# TopSheet.net
KiCad netlist of a schematic drawn in Altium Designer
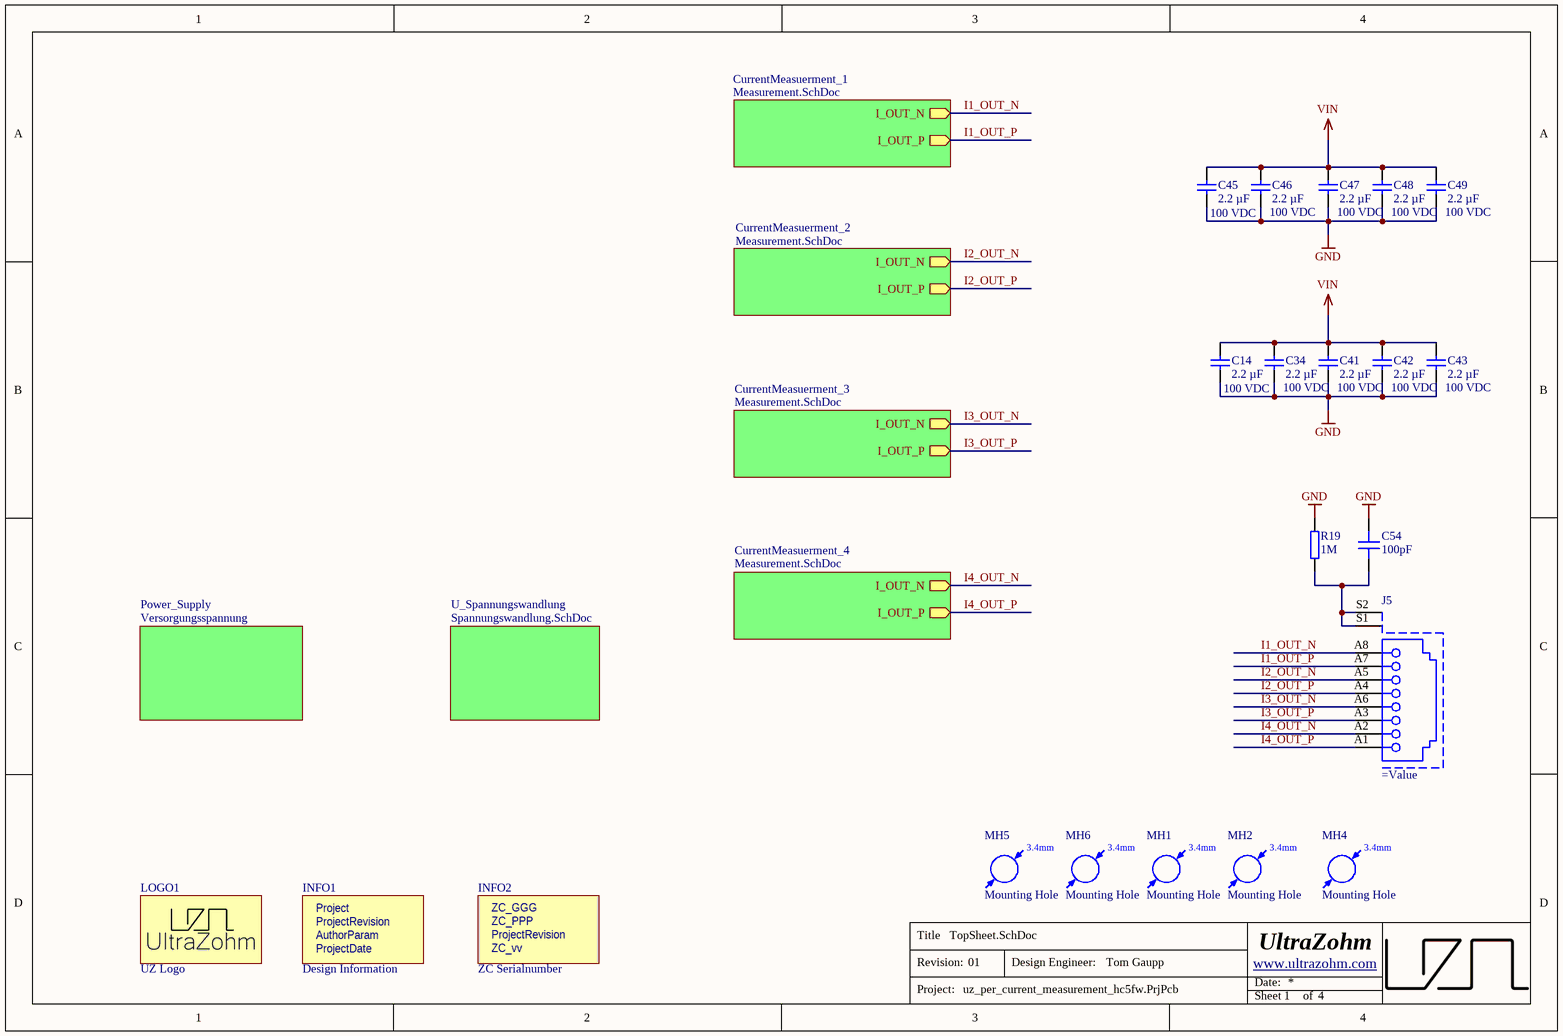
[diagram p0: TopSheet.SchDoc]

(export (version "E")
  (design (tool "Eeschema 10.0.6"))
  (components
    (comp (ref "C14")
      (value "2.2 µF")
      (footprint "C_1210_TE")
      (description "100V 2.2uF X7R ±10% 1210 Multilayer Ceramic Capacitors MLCC - SMD/SMT ROHS")
      (fields
        (field (name "MANUFACTURER PART NUMBER") "FS32X225K101EGG")
        (field (name "MANUFACTURER") "PSA(Prosperity Dielectrics)")
        (field (name "VOLTAGE RATING") "100 VDC")
        (field (name "CREATED FROM") "AGeiger")
      )
      (libsource (lib "user") (part "CAP-NP"))
    )
    (comp (ref "C34")
      (value "2.2 µF")
      (footprint "C_1210_TE")
      (description "100V 2.2uF X7R ±10% 1210 Multilayer Ceramic Capacitors MLCC - SMD/SMT ROHS")
      (fields
        (field (name "MANUFACTURER PART NUMBER") "FS32X225K101EGG")
        (field (name "MANUFACTURER") "PSA(Prosperity Dielectrics)")
        (field (name "VOLTAGE RATING") "100 VDC")
        (field (name "CREATED FROM") "AGeiger")
      )
      (libsource (lib "user") (part "CAP-NP"))
    )
    (comp (ref "C41")
      (value "2.2 µF")
      (footprint "C_1210_TE")
      (description "100V 2.2uF X7R ±10% 1210 Multilayer Ceramic Capacitors MLCC - SMD/SMT ROHS")
      (fields
        (field (name "MANUFACTURER PART NUMBER") "FS32X225K101EGG")
        (field (name "MANUFACTURER") "PSA(Prosperity Dielectrics)")
        (field (name "VOLTAGE RATING") "100 VDC")
        (field (name "CREATED FROM") "AGeiger")
      )
      (libsource (lib "user") (part "CAP-NP"))
    )
    (comp (ref "C42")
      (value "2.2 µF")
      (footprint "C_1210_TE")
      (description "100V 2.2uF X7R ±10% 1210 Multilayer Ceramic Capacitors MLCC - SMD/SMT ROHS")
      (fields
        (field (name "MANUFACTURER PART NUMBER") "FS32X225K101EGG")
        (field (name "MANUFACTURER") "PSA(Prosperity Dielectrics)")
        (field (name "VOLTAGE RATING") "100 VDC")
        (field (name "CREATED FROM") "AGeiger")
      )
      (libsource (lib "user") (part "CAP-NP"))
    )
    (comp (ref "C43")
      (value "2.2 µF")
      (footprint "C_1210_TE")
      (description "100V 2.2uF X7R ±10% 1210 Multilayer Ceramic Capacitors MLCC - SMD/SMT ROHS")
      (fields
        (field (name "MANUFACTURER PART NUMBER") "FS32X225K101EGG")
        (field (name "MANUFACTURER") "PSA(Prosperity Dielectrics)")
        (field (name "VOLTAGE RATING") "100 VDC")
        (field (name "CREATED FROM") "AGeiger")
      )
      (libsource (lib "user") (part "CAP-NP"))
    )
    (comp (ref "C45")
      (value "2.2 µF")
      (footprint "C_1210_TE")
      (description "100V 2.2uF X7R ±10% 1210 Multilayer Ceramic Capacitors MLCC - SMD/SMT ROHS")
      (fields
        (field (name "MANUFACTURER PART NUMBER") "FS32X225K101EGG")
        (field (name "MANUFACTURER") "PSA(Prosperity Dielectrics)")
        (field (name "VOLTAGE RATING") "100 VDC")
        (field (name "CREATED FROM") "AGeiger")
      )
      (libsource (lib "user") (part "CAP-NP"))
    )
    (comp (ref "C46")
      (value "2.2 µF")
      (footprint "C_1210_TE")
      (description "100V 2.2uF X7R ±10% 1210 Multilayer Ceramic Capacitors MLCC - SMD/SMT ROHS")
      (fields
        (field (name "MANUFACTURER PART NUMBER") "FS32X225K101EGG")
        (field (name "MANUFACTURER") "PSA(Prosperity Dielectrics)")
        (field (name "VOLTAGE RATING") "100 VDC")
        (field (name "CREATED FROM") "AGeiger")
      )
      (libsource (lib "user") (part "CAP-NP"))
    )
    (comp (ref "C47")
      (value "2.2 µF")
      (footprint "C_1210_TE")
      (description "100V 2.2uF X7R ±10% 1210 Multilayer Ceramic Capacitors MLCC - SMD/SMT ROHS")
      (fields
        (field (name "MANUFACTURER PART NUMBER") "FS32X225K101EGG")
        (field (name "MANUFACTURER") "PSA(Prosperity Dielectrics)")
        (field (name "VOLTAGE RATING") "100 VDC")
        (field (name "CREATED FROM") "AGeiger")
      )
      (libsource (lib "user") (part "CAP-NP"))
    )
    (comp (ref "C48")
      (value "2.2 µF")
      (footprint "C_1210_TE")
      (description "100V 2.2uF X7R ±10% 1210 Multilayer Ceramic Capacitors MLCC - SMD/SMT ROHS")
      (fields
        (field (name "MANUFACTURER PART NUMBER") "FS32X225K101EGG")
        (field (name "MANUFACTURER") "PSA(Prosperity Dielectrics)")
        (field (name "VOLTAGE RATING") "100 VDC")
        (field (name "CREATED FROM") "AGeiger")
      )
      (libsource (lib "user") (part "CAP-NP"))
    )
    (comp (ref "C49")
      (value "2.2 µF")
      (footprint "C_1210_TE")
      (description "100V 2.2uF X7R ±10% 1210 Multilayer Ceramic Capacitors MLCC - SMD/SMT ROHS")
      (fields
        (field (name "MANUFACTURER PART NUMBER") "FS32X225K101EGG")
        (field (name "MANUFACTURER") "PSA(Prosperity Dielectrics)")
        (field (name "VOLTAGE RATING") "100 VDC")
        (field (name "CREATED FROM") "AGeiger")
      )
      (libsource (lib "user") (part "CAP-NP"))
    )
    (comp (ref "C54")
      (value "100pF")
      (footprint "C_1206_TE")
      (description "100pF 1kV C0G ±5% 1206 Multilayer Ceramic Capacitors MLCC - SMD/SMT ROHS")
      (fields
        (field (name "MANUFACTURER PART NUMBER") "1206CG101J102NT")
        (field (name "MANUFACTURER") "FH (Guangdong Fenghua Advanced Tech)")
        (field (name "CREATED FROM") "TGaupp")
      )
      (libsource (lib "user") (part "Capacitor"))
    )
    (comp (ref "INFO1")
      (value "Design Information")
      (footprint "Design_info")
      (fields (field (name "MANUFACTURER") "UltraZohm") (field (name "CREATED FROM") "MGremer"))
      (libsource (lib "user") (part "Design_info"))
    )
    (comp (ref "INFO2")
      (value "ZC Serialnumber")
      (footprint "ZC-Serial")
      (fields
        (field (name "MANUFACTURER PART NUMBER") "ZC-Serial")
        (field (name "MANUFACTURER") "UltraZohm")
        (field (name "CREATED FROM") "FRosner")
      )
      (libsource (lib "user") (part "ZC_Serial"))
    )
    (comp (ref "J5")
      (value "~")
      (footprint "R-RJ45R10P-B000")
      (fields
        (field (name "MANUFACTURER PART NUMBER") "R-RJ45R10P-B000")
        (field (name "MANUFACTURER") "Ckmtw(Shenzhen Cankemeng)")
        (field (name "LCSC PART NUMBER") "C386758")
        (field (name "CREATED FROM") "KIlhan")
      )
      (libsource (lib "user") (part "R-RJ45R10P-B000"))
    )
    (comp (ref "LOGO1")
      (value "UZ Logo")
      (footprint "UZ_Logo_small")
      (fields
        (field (name "MANUFACTURER PART NUMBER") "Logo small")
        (field (name "MANUFACTURER") "UltraZohm")
        (field (name "CREATED") "Jan2021_Liegmann")
        (field (name "CREATED FROM") "MGremer")
      )
      (libsource (lib "user") (part "UZ Logo"))
    )
    (comp (ref "MH1")
      (value "Mounting Hole")
      (footprint "MH_3.4")
      (fields (field (name "CREATED FROM") "MHlatky"))
      (libsource (lib "user") (part "Mounting Hole"))
    )
    (comp (ref "MH2")
      (value "Mounting Hole")
      (footprint "MH_3.4")
      (fields (field (name "CREATED FROM") "MHlatky"))
      (libsource (lib "user") (part "Mounting Hole"))
    )
    (comp (ref "MH4")
      (value "Mounting Hole")
      (footprint "MH_3.4")
      (fields (field (name "CREATED FROM") "MHlatky"))
      (libsource (lib "user") (part "Mounting Hole"))
    )
    (comp (ref "MH5")
      (value "Mounting Hole")
      (footprint "MH_3.4")
      (fields (field (name "CREATED FROM") "MHlatky"))
      (libsource (lib "user") (part "Mounting Hole"))
    )
    (comp (ref "MH6")
      (value "Mounting Hole")
      (footprint "MH_3.4")
      (fields (field (name "CREATED FROM") "MHlatky"))
      (libsource (lib "user") (part "Mounting Hole"))
    )
    (comp (ref "R19")
      (value "1M")
      (footprint "RES 0603_1608")
      (description "SMD resistor 1%")
      (fields
        (field (name "MANUFACTURER PART NUMBER") "CRCW06031M00FKEAC")
        (field (name "MANUFACTURER") "Vishay / Dale")
        (field (name "CREATED FROM") "MGremer")
      )
      (libsource (lib "user") (part "Resistor"))
    )
  )
  (nets
    (net (code "1") (name "/I1_OUT_N") (class "Default")
      (node (ref "J5") (pin "A8") (pinfunction "A8_A8") (pintype "passive"))
    )
    (net (code "2") (name "/I1_OUT_P") (class "Default")
      (node (ref "J5") (pin "A7") (pinfunction "A7_A7") (pintype "passive"))
    )
    (net (code "3") (name "/I2_OUT_N") (class "Default")
      (node (ref "J5") (pin "A5") (pinfunction "A5_A5") (pintype "passive"))
    )
    (net (code "4") (name "/I2_OUT_P") (class "Default")
      (node (ref "J5") (pin "A4") (pinfunction "A4_A4") (pintype "passive"))
    )
    (net (code "5") (name "/I3_OUT_N") (class "Default")
      (node (ref "J5") (pin "A6") (pinfunction "A6_A6") (pintype "passive"))
    )
    (net (code "6") (name "/I3_OUT_P") (class "Default")
      (node (ref "J5") (pin "A3") (pinfunction "A3_A3") (pintype "passive"))
    )
    (net (code "7") (name "/I4_OUT_N") (class "Default")
      (node (ref "J5") (pin "A2") (pinfunction "A2_A2") (pintype "passive"))
    )
    (net (code "8") (name "/I4_OUT_P") (class "Default")
      (node (ref "J5") (pin "A1") (pinfunction "A1_A1") (pintype "passive"))
    )
    (net (code "9") (name "GND") (class "Default")
      (node (ref "C14") (pin "2") (pinfunction "2_2") (pintype "passive"))
      (node (ref "C34") (pin "2") (pinfunction "2_2") (pintype "passive"))
      (node (ref "C41") (pin "2") (pinfunction "2_2") (pintype "passive"))
      (node (ref "C42") (pin "2") (pinfunction "2_2") (pintype "passive"))
      (node (ref "C43") (pin "2") (pinfunction "2_2") (pintype "passive"))
      (node (ref "C45") (pin "2") (pinfunction "2_2") (pintype "passive"))
      (node (ref "C46") (pin "2") (pinfunction "2_2") (pintype "passive"))
      (node (ref "C47") (pin "2") (pinfunction "2_2") (pintype "passive"))
      (node (ref "C48") (pin "2") (pinfunction "2_2") (pintype "passive"))
      (node (ref "C49") (pin "2") (pinfunction "2_2") (pintype "passive"))
      (node (ref "C54") (pin "2") (pinfunction "2_2") (pintype "passive"))
      (node (ref "R19") (pin "2") (pinfunction "2_2") (pintype "passive"))
    )
    (net (code "10") (name "Net-(C54-Pad1)") (class "Default")
      (node (ref "C54") (pin "1") (pinfunction "1_1") (pintype "passive"))
      (node (ref "J5") (pin "S1") (pinfunction "S1_S1") (pintype "passive"))
      (node (ref "J5") (pin "S2") (pinfunction "S2_S2") (pintype "passive"))
      (node (ref "R19") (pin "1") (pinfunction "1_1") (pintype "passive"))
    )
    (net (code "11") (name "VIN") (class "Default")
      (node (ref "C14") (pin "1") (pinfunction "1_1") (pintype "passive"))
      (node (ref "C34") (pin "1") (pinfunction "1_1") (pintype "passive"))
      (node (ref "C41") (pin "1") (pinfunction "1_1") (pintype "passive"))
      (node (ref "C42") (pin "1") (pinfunction "1_1") (pintype "passive"))
      (node (ref "C43") (pin "1") (pinfunction "1_1") (pintype "passive"))
      (node (ref "C45") (pin "1") (pinfunction "1_1") (pintype "passive"))
      (node (ref "C46") (pin "1") (pinfunction "1_1") (pintype "passive"))
      (node (ref "C47") (pin "1") (pinfunction "1_1") (pintype "passive"))
      (node (ref "C48") (pin "1") (pinfunction "1_1") (pintype "passive"))
      (node (ref "C49") (pin "1") (pinfunction "1_1") (pintype "passive"))
    )
  )
)
